# SparkFun_LilyPad-Switched-Battery_Stakin.net
KiCad netlist of a schematic drawn in EAGLE
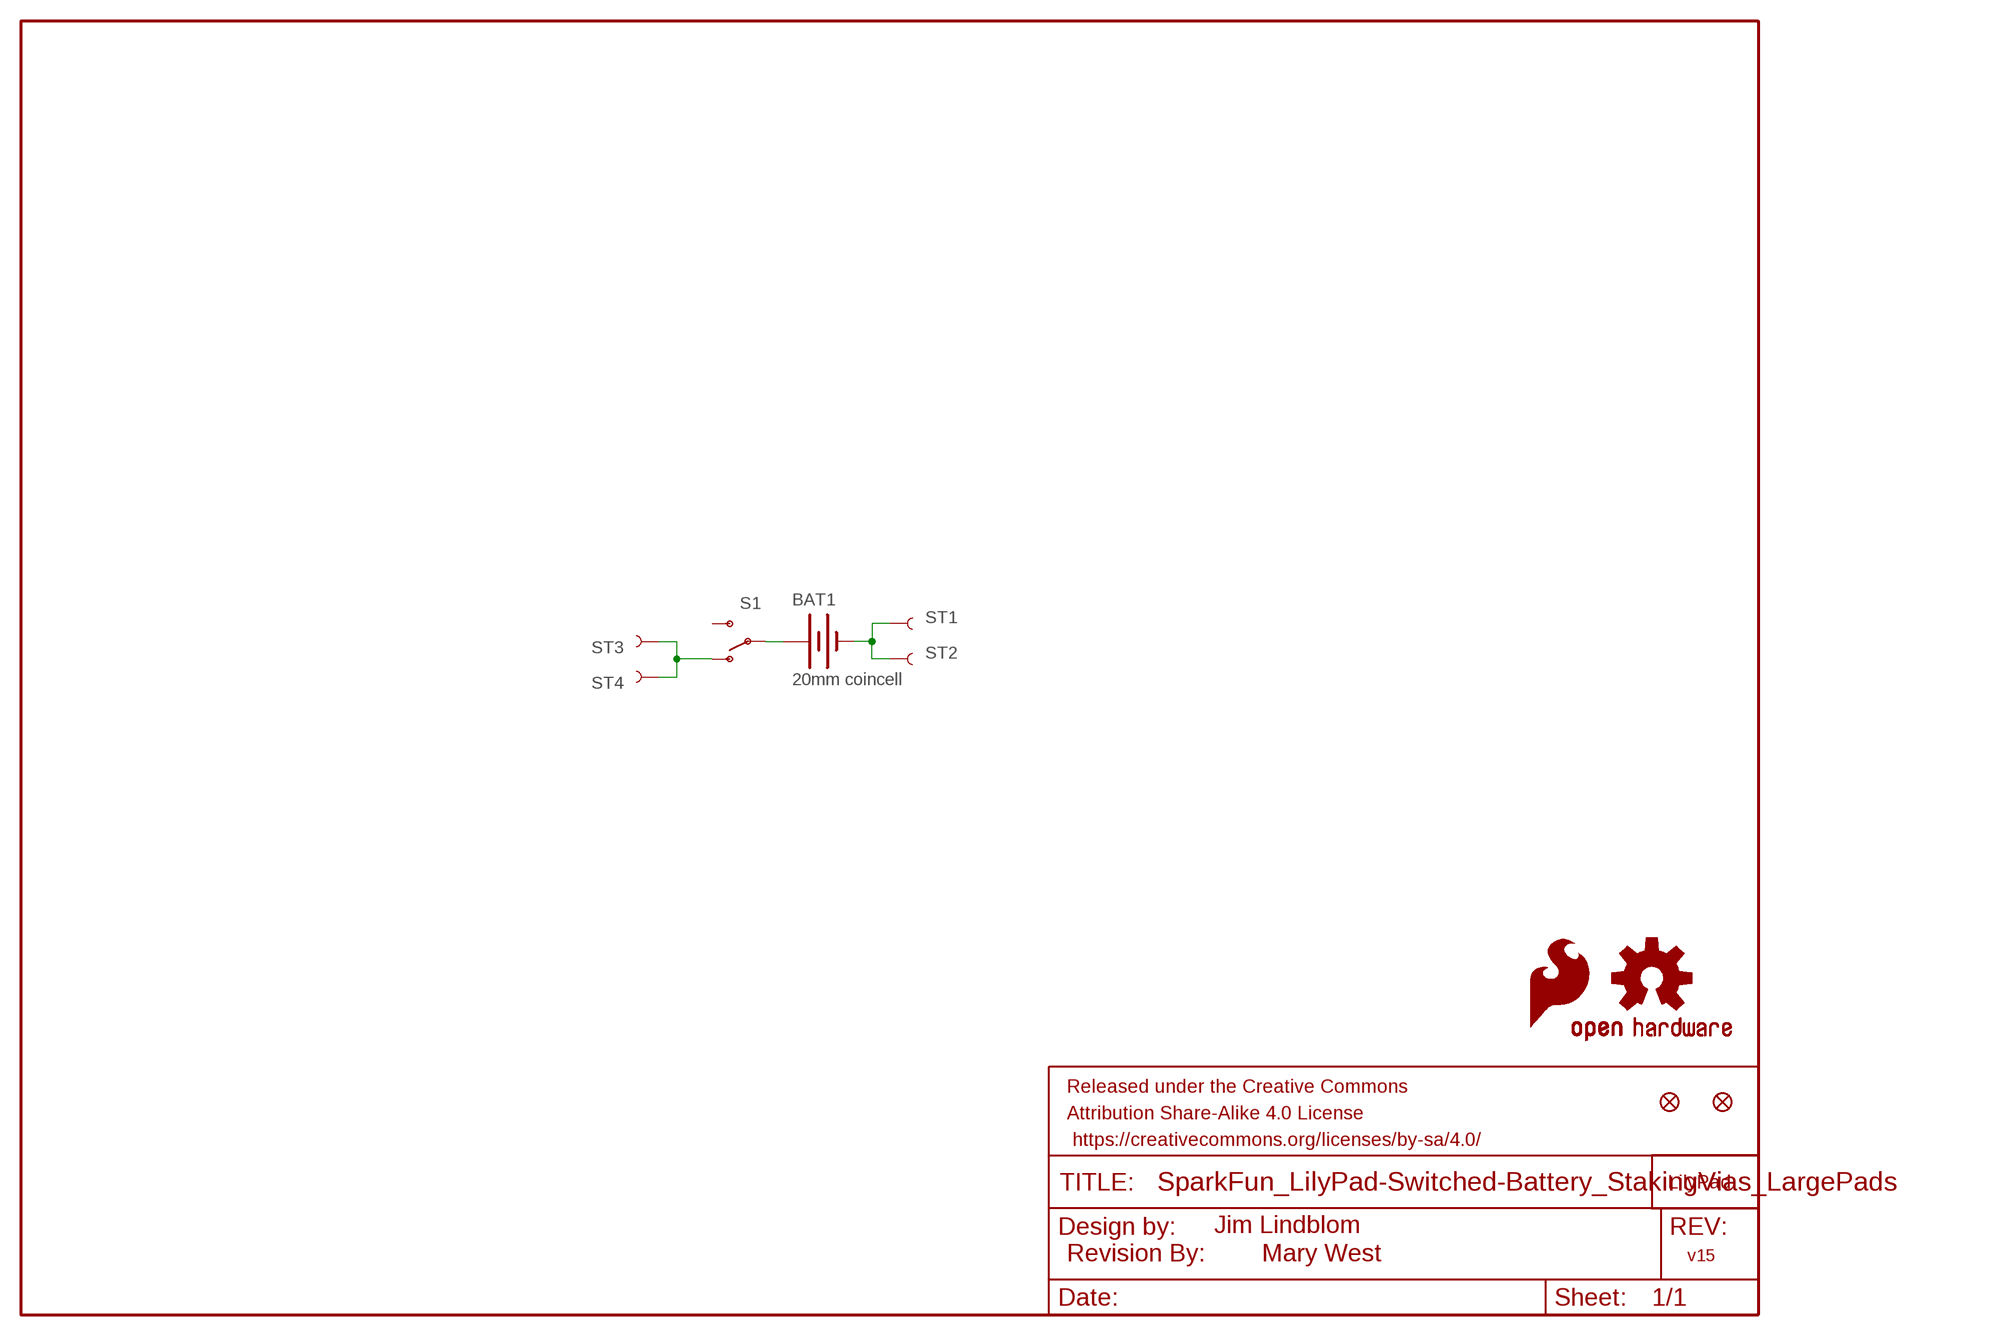
[diagram p0: schematic, sheet 1]

(export (version "E")
  (design (tool "Eeschema 10.0.6"))
  (components
    (comp (ref "BAT1")
      (value "20mm coincell")
      (footprint "eagle-import:BATTCON_20MM_4LEGS")
      (libsource (lib "eagle-import") (part "BATTERY20MM_4LEGS"))
    )
    (comp (ref "FRAME1")
      (value "FRAME-LETTER")
      (footprint "eagle-import:CREATIVE_COMMONS")
      (libsource (lib "eagle-import") (part "FRAME-LETTER"))
    )
    (comp (ref "JP1")
      (value "FIDUCIALUFIDUCIAL")
      (footprint "eagle-import:MICRO-FIDUCIAL")
      (libsource (lib "eagle-import") (part "FIDUCIALUFIDUCIAL"))
    )
    (comp (ref "JP2")
      (value "FIDUCIALUFIDUCIAL")
      (footprint "eagle-import:MICRO-FIDUCIAL")
      (libsource (lib "eagle-import") (part "FIDUCIALUFIDUCIAL"))
    )
    (comp (ref "LOGO1")
      (value "SFE_LOGO_FLAME.1_INCH")
      (footprint "eagle-import:SFE_LOGO_FLAME_.1")
      (libsource (lib "eagle-import") (part "SFE_LOGO_FLAME.1_INCH"))
    )
    (comp (ref "S1")
      (value "SWITCH-SPDTSMD")
      (footprint "eagle-import:AYZ0202")
      (libsource (lib "eagle-import") (part "SWITCH-SPDTSMD"))
    )
    (comp (ref "ST1")
      (value "SEWTAP6")
      (footprint "eagle-import:PETAL-SMALL-2SIDE")
      (libsource (lib "eagle-import") (part "SEWTAP6"))
    )
    (comp (ref "ST2")
      (value "SEWTAP6")
      (footprint "eagle-import:PETAL-SMALL-2SIDE")
      (libsource (lib "eagle-import") (part "SEWTAP6"))
    )
    (comp (ref "ST3")
      (value "SEWTAP6")
      (footprint "eagle-import:PETAL-SMALL-2SIDE")
      (libsource (lib "eagle-import") (part "SEWTAP6"))
    )
    (comp (ref "ST4")
      (value "SEWTAP6")
      (footprint "eagle-import:PETAL-SMALL-2SIDE")
      (libsource (lib "eagle-import") (part "SEWTAP6"))
    )
    (comp (ref "U$1")
      (value "REVISION")
      (footprint "eagle-import:REVISION")
      (libsource (lib "eagle-import") (part "REVISION"))
    )
    (comp (ref "U$5")
      (value "LOGO-LPLP")
      (footprint "eagle-import:LOGO-LILYPAD")
      (libsource (lib "eagle-import") (part "LOGO-LPLP"))
    )
    (comp (ref "U$7")
      (value "OSHW-LOGOS")
      (footprint "eagle-import:OSHW-LOGO-S")
      (libsource (lib "eagle-import") (part "OSHW-LOGOS"))
    )
  )
  (nets
    (net (code "1") (name "Net-(BAT1--)") (class "Default")
      (node (ref "BAT1") (pin "NEGATIVE") (pinfunction "-_NEGATIVE") (pintype "power_in"))
      (node (ref "ST1") (pin "1") (pinfunction "1_1") (pintype "bidirectional"))
      (node (ref "ST2") (pin "1") (pinfunction "1_1") (pintype "bidirectional"))
    )
    (net (code "2") (name "Net-(S1-O)") (class "Default")
      (node (ref "S1") (pin "1") (pinfunction "O_1") (pintype "passive"))
      (node (ref "ST3") (pin "1") (pinfunction "1_1") (pintype "bidirectional"))
      (node (ref "ST4") (pin "1") (pinfunction "1_1") (pintype "bidirectional"))
    )
    (net (code "3") (name "Net-(S1-P)") (class "Default")
      (node (ref "BAT1") (pin "POSITIVE@1") (pinfunction "+_POSITIVE@1") (pintype "power_in"))
      (node (ref "BAT1") (pin "POSITIVE@2") (pinfunction "+_POSITIVE@2") (pintype "power_in"))
      (node (ref "BAT1") (pin "POSITIVE@3") (pinfunction "+_POSITIVE@3") (pintype "power_in"))
      (node (ref "BAT1") (pin "POSITIVE@4") (pinfunction "+_POSITIVE@4") (pintype "power_in"))
      (node (ref "S1") (pin "2") (pinfunction "P_2") (pintype "passive"))
    )
    (net (code "4") (name "unconnected-(S1-S-Pad3)") (class "Default")
      (node (ref "S1") (pin "3") (pinfunction "S_3") (pintype "passive"))
    )
  )
)
